# 18__-2.net
KiCad netlist of a schematic drawn in Altium Designer
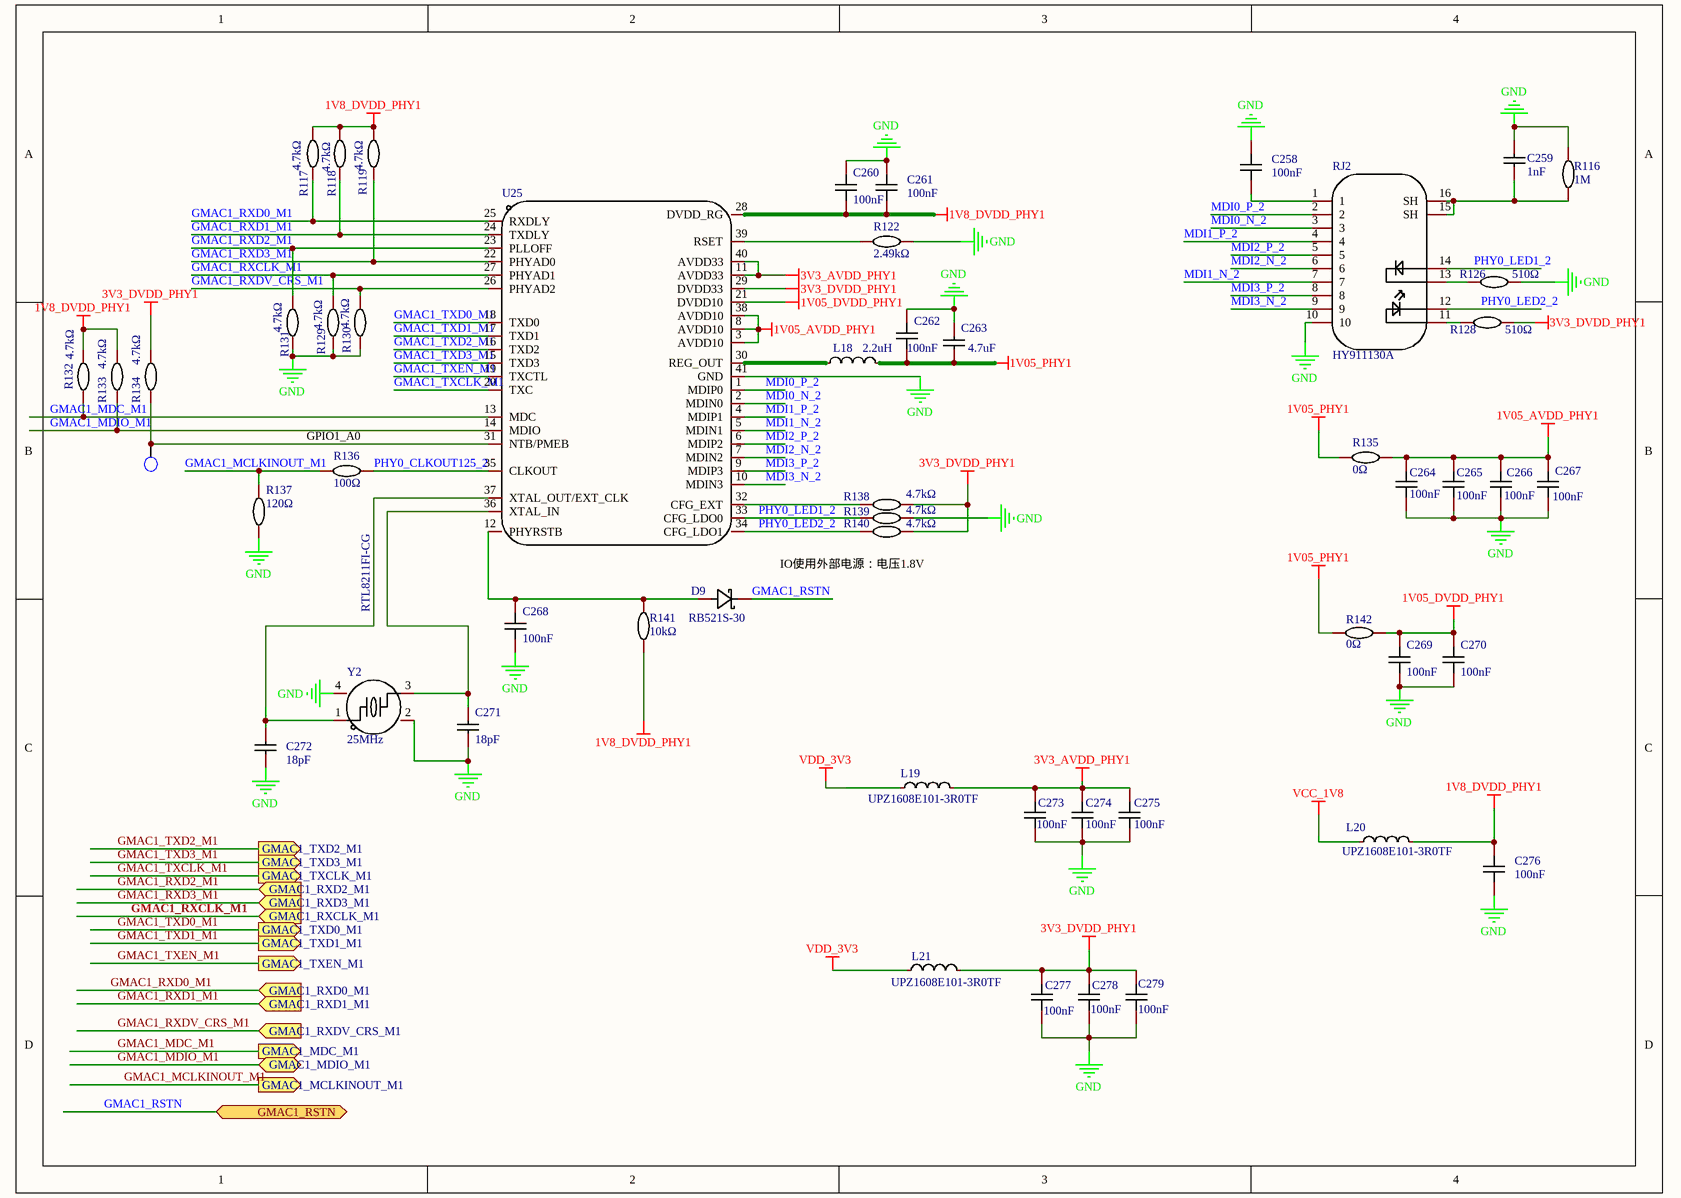
[diagram p0: 18_网口接口-2.schdoc]

(export (version "E")
  (design (tool "Eeschema 10.0.6"))
  (components
    (comp (ref "C258")
      (value "100nF")
      (footprint "C0603")
      (fields
        (field (name "NAME") "100nF")
        (field (name "MANUFACTURER") "YAGEO(国巨)")
        (field (name "MANUFACTURER PART") "CC0603KRX7R9BB104")
        (field (name "TOLERANCE") "±10%")
      )
      (libsource (lib "altium-import") (part "root_1_CC0603KRX7R9BB104_"))
    )
    (comp (ref "C259")
      (value "1nF")
      (footprint "C0603")
      (fields
        (field (name "NAME") "1nF")
        (field (name "MANUFACTURER") "YAGEO(国巨)")
        (field (name "MANUFACTURER PART") "CC0603KRX7R9BB102")
        (field (name "TOLERANCE") "±10%")
      )
      (libsource (lib "altium-import") (part "root_3_CC0603KRX7R9BB102_"))
    )
    (comp (ref "C260")
      (value "100nF")
      (footprint "C0603")
      (fields
        (field (name "NAME") "100nF")
        (field (name "MANUFACTURER") "YAGEO(国巨)")
        (field (name "MANUFACTURER PART") "CC0603KRX7R9BB104")
        (field (name "TOLERANCE") "±10%")
      )
      (libsource (lib "altium-import") (part "root_1_CC0603KRX7R9BB104_"))
    )
    (comp (ref "C261")
      (value "100nF")
      (footprint "C0603")
      (fields
        (field (name "NAME") "100nF")
        (field (name "MANUFACTURER") "YAGEO(国巨)")
        (field (name "MANUFACTURER PART") "CC0603KRX7R9BB104")
        (field (name "TOLERANCE") "±10%")
      )
      (libsource (lib "altium-import") (part "root_1_CC0603KRX7R9BB104_"))
    )
    (comp (ref "C262")
      (value "100nF")
      (footprint "C0603")
      (fields
        (field (name "NAME") "100nF")
        (field (name "MANUFACTURER") "YAGEO(国巨)")
        (field (name "MANUFACTURER PART") "CC0603KRX7R9BB104")
        (field (name "TOLERANCE") "±10%")
      )
      (libsource (lib "altium-import") (part "root_1_CC0603KRX7R9BB104_"))
    )
    (comp (ref "C263")
      (value "4.7uF")
      (footprint "C0603")
      (fields
        (field (name "NAME") "4.7uF")
        (field (name "MANUFACTURER PART") "CL10A475KO8NNNC")
        (field (name "MANUFACTURER") "SAMSUNG(三星)")
        (field (name "TOLERANCE") "±10%")
      )
      (libsource (lib "altium-import") (part "root_1_CL10A475KO8NNNC_"))
    )
    (comp (ref "C264")
      (value "100nF")
      (footprint "C0603")
      (fields
        (field (name "NAME") "100nF")
        (field (name "MANUFACTURER") "YAGEO(国巨)")
        (field (name "MANUFACTURER PART") "CC0603KRX7R9BB104")
        (field (name "TOLERANCE") "±10%")
      )
      (libsource (lib "altium-import") (part "root_1_CC0603KRX7R9BB104_"))
    )
    (comp (ref "C265")
      (value "100nF")
      (footprint "C0603")
      (fields
        (field (name "NAME") "100nF")
        (field (name "MANUFACTURER") "YAGEO(国巨)")
        (field (name "MANUFACTURER PART") "CC0603KRX7R9BB104")
        (field (name "TOLERANCE") "±10%")
      )
      (libsource (lib "altium-import") (part "root_1_CC0603KRX7R9BB104_"))
    )
    (comp (ref "C266")
      (value "100nF")
      (footprint "C0603")
      (fields
        (field (name "NAME") "100nF")
        (field (name "MANUFACTURER") "YAGEO(国巨)")
        (field (name "MANUFACTURER PART") "CC0603KRX7R9BB104")
        (field (name "TOLERANCE") "±10%")
      )
      (libsource (lib "altium-import") (part "root_1_CC0603KRX7R9BB104_"))
    )
    (comp (ref "C267")
      (value "100nF")
      (footprint "C0603")
      (fields
        (field (name "NAME") "100nF")
        (field (name "MANUFACTURER") "YAGEO(国巨)")
        (field (name "MANUFACTURER PART") "CC0603KRX7R9BB104")
        (field (name "TOLERANCE") "±10%")
      )
      (libsource (lib "altium-import") (part "root_1_CC0603KRX7R9BB104_"))
    )
    (comp (ref "C268")
      (value "100nF")
      (footprint "C0603")
      (fields
        (field (name "NAME") "100nF")
        (field (name "MANUFACTURER") "YAGEO(国巨)")
        (field (name "MANUFACTURER PART") "CC0603KRX7R9BB104")
        (field (name "TOLERANCE") "±10%")
      )
      (libsource (lib "altium-import") (part "root_1_CC0603KRX7R9BB104_"))
    )
    (comp (ref "C269")
      (value "100nF")
      (footprint "C0603")
      (fields
        (field (name "NAME") "100nF")
        (field (name "MANUFACTURER") "YAGEO(国巨)")
        (field (name "MANUFACTURER PART") "CC0603KRX7R9BB104")
        (field (name "TOLERANCE") "±10%")
      )
      (libsource (lib "altium-import") (part "root_1_CC0603KRX7R9BB104_"))
    )
    (comp (ref "C270")
      (value "100nF")
      (footprint "C0603")
      (fields
        (field (name "NAME") "100nF")
        (field (name "MANUFACTURER") "YAGEO(国巨)")
        (field (name "MANUFACTURER PART") "CC0603KRX7R9BB104")
        (field (name "TOLERANCE") "±10%")
      )
      (libsource (lib "altium-import") (part "root_1_CC0603KRX7R9BB104_"))
    )
    (comp (ref "C271")
      (value "18pF")
      (footprint "C0603")
      (fields
        (field (name "NAME") "18pF")
        (field (name "MANUFACTURER") "SAMSUNG(三星)")
        (field (name "MANUFACTURER PART") "CL10C180JB8NNNC")
        (field (name "TOLERANCE") "±5%")
      )
      (libsource (lib "altium-import") (part "root_3_CL10C180JB8NNNC_"))
    )
    (comp (ref "C272")
      (value "18pF")
      (footprint "C0603")
      (fields
        (field (name "NAME") "18pF")
        (field (name "MANUFACTURER") "SAMSUNG(三星)")
        (field (name "MANUFACTURER PART") "CL10C180JB8NNNC")
        (field (name "TOLERANCE") "±5%")
      )
      (libsource (lib "altium-import") (part "root_3_CL10C180JB8NNNC_"))
    )
    (comp (ref "C273")
      (value "100nF")
      (footprint "C0603")
      (fields
        (field (name "NAME") "100nF")
        (field (name "MANUFACTURER") "YAGEO(国巨)")
        (field (name "MANUFACTURER PART") "CC0603KRX7R9BB104")
        (field (name "TOLERANCE") "±10%")
      )
      (libsource (lib "altium-import") (part "root_1_CC0603KRX7R9BB104_"))
    )
    (comp (ref "C274")
      (value "100nF")
      (footprint "C0603")
      (fields
        (field (name "NAME") "100nF")
        (field (name "MANUFACTURER") "YAGEO(国巨)")
        (field (name "MANUFACTURER PART") "CC0603KRX7R9BB104")
        (field (name "TOLERANCE") "±10%")
      )
      (libsource (lib "altium-import") (part "root_1_CC0603KRX7R9BB104_"))
    )
    (comp (ref "C275")
      (value "100nF")
      (footprint "C0603")
      (fields
        (field (name "NAME") "100nF")
        (field (name "MANUFACTURER") "YAGEO(国巨)")
        (field (name "MANUFACTURER PART") "CC0603KRX7R9BB104")
        (field (name "TOLERANCE") "±10%")
      )
      (libsource (lib "altium-import") (part "root_1_CC0603KRX7R9BB104_"))
    )
    (comp (ref "C276")
      (value "100nF")
      (footprint "C0603")
      (fields
        (field (name "NAME") "100nF")
        (field (name "MANUFACTURER") "YAGEO(国巨)")
        (field (name "MANUFACTURER PART") "CC0603KRX7R9BB104")
        (field (name "TOLERANCE") "±10%")
      )
      (libsource (lib "altium-import") (part "root_1_CC0603KRX7R9BB104_"))
    )
    (comp (ref "C277")
      (value "100nF")
      (footprint "C0603")
      (fields
        (field (name "NAME") "100nF")
        (field (name "MANUFACTURER") "YAGEO(国巨)")
        (field (name "MANUFACTURER PART") "CC0603KRX7R9BB104")
        (field (name "TOLERANCE") "±10%")
      )
      (libsource (lib "altium-import") (part "root_1_CC0603KRX7R9BB104_"))
    )
    (comp (ref "C278")
      (value "100nF")
      (footprint "C0603")
      (fields
        (field (name "NAME") "100nF")
        (field (name "MANUFACTURER") "YAGEO(国巨)")
        (field (name "MANUFACTURER PART") "CC0603KRX7R9BB104")
        (field (name "TOLERANCE") "±10%")
      )
      (libsource (lib "altium-import") (part "root_1_CC0603KRX7R9BB104_"))
    )
    (comp (ref "C279")
      (value "100nF")
      (footprint "C0603")
      (fields
        (field (name "NAME") "100nF")
        (field (name "MANUFACTURER") "YAGEO(国巨)")
        (field (name "MANUFACTURER PART") "CC0603KRX7R9BB104")
        (field (name "TOLERANCE") "±10%")
      )
      (libsource (lib "altium-import") (part "root_1_CC0603KRX7R9BB104_"))
    )
    (comp (ref "D9")
      (value "RB521S-30")
      (footprint "SOD-523_L1.2-W0.8-LS1.6-RD")
      (fields (field (name "NAME") "RB521S-30") (field (name "MANUFACTURER") "TWGMC(台湾迪嘉)"))
      (libsource (lib "altium-import") (part "root_2_RB521S-30_C727120_"))
    )
    (comp (ref "L18")
      (value "2.2uH")
      (footprint "IND-SMD_L2.5-W2.0-VLS252012CX-150M")
      (fields
        (field (name "NAME") "2.2uH")
        (field (name "MANUFACTURER") "cjiang(长江微电)")
        (field (name "MANUFACTURER PART") "FXLB252012-2R2-M")
        (field (name "TOLERANCE") "±20%")
      )
      (libsource (lib "altium-import") (part "root_0_FXLB252012-2R2-M_"))
    )
    (comp (ref "L19")
      (value "UPZ1608E101-3R0TF")
      (footprint "L0603")
      (fields
        (field (name "NAME") "UPZ1608E101-3R0TF")
        (field (name "MANUFACTURER") "Sunlord(顺络)")
        (field (name "TOLERANCE") "±25%")
      )
      (libsource (lib "altium-import") (part "root_0_mirrored_UPZ1608E101-3R0TF_"))
    )
    (comp (ref "L20")
      (value "UPZ1608E101-3R0TF")
      (footprint "L0603")
      (fields
        (field (name "NAME") "UPZ1608E101-3R0TF")
        (field (name "MANUFACTURER") "Sunlord(顺络)")
        (field (name "TOLERANCE") "±25%")
      )
      (libsource (lib "altium-import") (part "root_0_mirrored_UPZ1608E101-3R0TF_"))
    )
    (comp (ref "L21")
      (value "UPZ1608E101-3R0TF")
      (footprint "L0603")
      (fields
        (field (name "NAME") "UPZ1608E101-3R0TF")
        (field (name "MANUFACTURER") "Sunlord(顺络)")
        (field (name "TOLERANCE") "±25%")
      )
      (libsource (lib "altium-import") (part "root_0_mirrored_UPZ1608E101-3R0TF_"))
    )
    (comp (ref "R116")
      (value "1M")
      (footprint "R0805")
      (fields (field (name "NAME") "1M"))
      (libsource (lib "altium-import") (part "root_3_Res_0805_"))
    )
    (comp (ref "R117")
      (value "4.7kΩ")
      (footprint "R0603")
      (fields
        (field (name "NAME") "4.7kΩ")
        (field (name "MANUFACTURER") "UNI-ROYAL(厚声)")
        (field (name "MANUFACTURER PART") "0603WAF4701T5E")
        (field (name "TOLERANCE") "±1%")
      )
      (libsource (lib "altium-import") (part "root_1_0603WAF4701T5E_"))
    )
    (comp (ref "R118")
      (value "4.7kΩ")
      (footprint "R0603")
      (fields
        (field (name "NAME") "4.7kΩ")
        (field (name "MANUFACTURER") "UNI-ROYAL(厚声)")
        (field (name "MANUFACTURER PART") "0603WAF4701T5E")
        (field (name "TOLERANCE") "±1%")
      )
      (libsource (lib "altium-import") (part "root_1_0603WAF4701T5E_"))
    )
    (comp (ref "R119")
      (value "4.7kΩ")
      (footprint "R0603")
      (fields
        (field (name "NAME") "4.7kΩ")
        (field (name "MANUFACTURER") "UNI-ROYAL(厚声)")
        (field (name "MANUFACTURER PART") "0603WAF4701T5E")
        (field (name "TOLERANCE") "±1%")
      )
      (libsource (lib "altium-import") (part "root_1_0603WAF4701T5E_"))
    )
    (comp (ref "R122")
      (value "2.49kΩ")
      (footprint "R0603")
      (fields
        (field (name "NAME") "2.49kΩ")
        (field (name "MANUFACTURER") "UNI-ROYAL(厚声)")
        (field (name "MANUFACTURER PART") "0603WAF2491T5E")
        (field (name "TOLERANCE") "±1%")
      )
      (libsource (lib "altium-import") (part "root_0_0603WAF2491T5E_"))
    )
    (comp (ref "R126")
      (value "510Ω")
      (footprint "R0603")
      (fields
        (field (name "NAME") "510Ω")
        (field (name "MANUFACTURER") "UNI-ROYAL(厚声)")
        (field (name "MANUFACTURER PART") "0603WAF5100T5E")
        (field (name "TOLERANCE") "±1%")
      )
      (libsource (lib "altium-import") (part "root_0_0603WAF5100T5E_"))
    )
    (comp (ref "R128")
      (value "510Ω")
      (footprint "R0603")
      (fields
        (field (name "NAME") "510Ω")
        (field (name "MANUFACTURER") "UNI-ROYAL(厚声)")
        (field (name "MANUFACTURER PART") "0603WAF5100T5E")
        (field (name "TOLERANCE") "±1%")
      )
      (libsource (lib "altium-import") (part "root_0_0603WAF5100T5E_"))
    )
    (comp (ref "R129")
      (value "4.7kΩ")
      (footprint "R0603")
      (fields
        (field (name "NAME") "4.7kΩ")
        (field (name "MANUFACTURER") "UNI-ROYAL(厚声)")
        (field (name "MANUFACTURER PART") "0603WAF4701T5E")
        (field (name "TOLERANCE") "±1%")
      )
      (libsource (lib "altium-import") (part "root_1_0603WAF4701T5E_"))
    )
    (comp (ref "R130")
      (value "4.7kΩ")
      (footprint "R0603")
      (fields
        (field (name "NAME") "4.7kΩ")
        (field (name "MANUFACTURER") "UNI-ROYAL(厚声)")
        (field (name "MANUFACTURER PART") "0603WAF4701T5E")
        (field (name "TOLERANCE") "±1%")
      )
      (libsource (lib "altium-import") (part "root_1_0603WAF4701T5E_"))
    )
    (comp (ref "R131")
      (value "4.7kΩ")
      (footprint "R0603")
      (fields
        (field (name "NAME") "4.7kΩ")
        (field (name "MANUFACTURER") "UNI-ROYAL(厚声)")
        (field (name "MANUFACTURER PART") "0603WAF4701T5E")
        (field (name "TOLERANCE") "±1%")
      )
      (libsource (lib "altium-import") (part "root_1_0603WAF4701T5E_"))
    )
    (comp (ref "R132")
      (value "4.7kΩ")
      (footprint "R0603")
      (fields
        (field (name "NAME") "4.7kΩ")
        (field (name "MANUFACTURER") "UNI-ROYAL(厚声)")
        (field (name "MANUFACTURER PART") "0603WAF4701T5E")
        (field (name "TOLERANCE") "±1%")
      )
      (libsource (lib "altium-import") (part "root_1_0603WAF4701T5E_"))
    )
    (comp (ref "R133")
      (value "4.7kΩ")
      (footprint "R0603")
      (fields
        (field (name "NAME") "4.7kΩ")
        (field (name "MANUFACTURER") "UNI-ROYAL(厚声)")
        (field (name "MANUFACTURER PART") "0603WAF4701T5E")
        (field (name "TOLERANCE") "±1%")
      )
      (libsource (lib "altium-import") (part "root_1_0603WAF4701T5E_"))
    )
    (comp (ref "R134")
      (value "4.7kΩ")
      (footprint "R0603")
      (fields
        (field (name "NAME") "4.7kΩ")
        (field (name "MANUFACTURER") "UNI-ROYAL(厚声)")
        (field (name "MANUFACTURER PART") "0603WAF4701T5E")
        (field (name "TOLERANCE") "±1%")
      )
      (libsource (lib "altium-import") (part "root_1_0603WAF4701T5E_"))
    )
    (comp (ref "R135")
      (value "0Ω")
      (footprint "R0603")
      (fields
        (field (name "NAME") "0Ω")
        (field (name "MANUFACTURER") "UNI-ROYAL(厚声)")
        (field (name "MANUFACTURER PART") "0603WAF0000T5E")
        (field (name "TOLERANCE") "±1%")
      )
      (libsource (lib "altium-import") (part "root_0_0603WAF0000T5E_"))
    )
    (comp (ref "R136")
      (value "100Ω")
      (footprint "R0603")
      (fields
        (field (name "NAME") "100Ω")
        (field (name "MANUFACTURER") "UNI-ROYAL(厚声)")
        (field (name "MANUFACTURER PART") "0603WAF1000T5E")
        (field (name "TOLERANCE") "±1%")
      )
      (libsource (lib "altium-import") (part "root_0_0603WAF1000T5E_"))
    )
    (comp (ref "R137")
      (value "120Ω")
      (footprint "R0603")
      (fields
        (field (name "NAME") "120Ω")
        (field (name "MANUFACTURER") "UNI-ROYAL(厚声)")
        (field (name "MANUFACTURER PART") "0603WAF1200T5E")
        (field (name "TOLERANCE") "±1%")
      )
      (libsource (lib "altium-import") (part "root_1_0603WAF1200T5E_"))
    )
    (comp (ref "R138")
      (value "4.7kΩ")
      (footprint "R0603")
      (fields
        (field (name "NAME") "4.7kΩ")
        (field (name "MANUFACTURER") "UNI-ROYAL(厚声)")
        (field (name "MANUFACTURER PART") "0603WAF4701T5E")
        (field (name "TOLERANCE") "±1%")
      )
      (libsource (lib "altium-import") (part "root_0_0603WAF4701T5E_"))
    )
    (comp (ref "R139")
      (value "4.7kΩ")
      (footprint "R0603")
      (fields
        (field (name "NAME") "4.7kΩ")
        (field (name "MANUFACTURER") "UNI-ROYAL(厚声)")
        (field (name "MANUFACTURER PART") "0603WAF4701T5E")
        (field (name "TOLERANCE") "±1%")
      )
      (libsource (lib "altium-import") (part "root_0_0603WAF4701T5E_"))
    )
    (comp (ref "R140")
      (value "4.7kΩ")
      (footprint "R0603")
      (fields
        (field (name "NAME") "4.7kΩ")
        (field (name "MANUFACTURER") "UNI-ROYAL(厚声)")
        (field (name "MANUFACTURER PART") "0603WAF4701T5E")
        (field (name "TOLERANCE") "±1%")
      )
      (libsource (lib "altium-import") (part "root_0_0603WAF4701T5E_"))
    )
    (comp (ref "R141")
      (value "10kΩ")
      (footprint "R0603")
      (fields
        (field (name "NAME") "10kΩ")
        (field (name "MANUFACTURER") "UNI-ROYAL(厚声)")
        (field (name "MANUFACTURER PART") "0603WAF1002T5E")
        (field (name "TOLERANCE") "±1%")
      )
      (libsource (lib "altium-import") (part "root_3_0603WAF1002T5E_"))
    )
    (comp (ref "R142")
      (value "0Ω")
      (footprint "R0603")
      (fields
        (field (name "NAME") "0Ω")
        (field (name "MANUFACTURER") "UNI-ROYAL(厚声)")
        (field (name "MANUFACTURER PART") "0603WAF0000T5E")
        (field (name "TOLERANCE") "±1%")
      )
      (libsource (lib "altium-import") (part "root_2_0603WAF0000T5E_"))
    )
    (comp (ref "RJ2")
      (value "HY911130A")
      (footprint "RJ45-TH_10P-P2.54-S2.54_L16.1-W21.4_HY911130A")
      (fields (field (name "NAME") "HY911130A") (field (name "MANUFACTURER") "HANRUN(汉仁)"))
      (libsource (lib "altium-import") (part "root_0_HY911130A_"))
    )
    (comp (ref "TP2") (value "TP") (footprint "TP_0R70") (libsource (lib "RK3568核心板") (part "TP")))
    (comp (ref "U25")
      (value "RTL8211FI-CG")
      (footprint "QFN-40_L5.0-W5.0-P0.40-BL-EP3.7")
      (fields (field (name "NAME") "RTL8211FI-CG") (field (name "MANUFACTURER") "REALTEK(瑞昱)"))
      (libsource (lib "altium-import") (part "root_0_RTL8211FI-CG_"))
    )
    (comp (ref "Y2")
      (value "25MHz")
      (footprint "CRYSTAL-SMD_4P-L3.2-W2.5-BL")
      (fields
        (field (name "NAME") "25MHz")
        (field (name "MANUFACTURER") "YXC(扬兴晶振)")
        (field (name "MANUFACTURER PART") "XL2EL89CSI-111YLC-25M")
      )
      (libsource (lib "altium-import") (part "root_0_XL2EL89CSI-111YLC-25M_"))
    )
  )
  (nets
    (net (code "1") (name "/GMAC1_MCLKINOUT_M1") (class "Default")
      (node (ref "R136") (pin "1") (pinfunction "1_1") (pintype "passive"))
      (node (ref "R137") (pin "2") (pinfunction "2_2") (pintype "passive"))
    )
    (net (code "2") (name "/GMAC1_MDC_M1") (class "Default")
      (node (ref "R132") (pin "1") (pinfunction "1_1") (pintype "passive"))
      (node (ref "U25") (pin "13") (pinfunction "MDC_13") (pintype "passive"))
    )
    (net (code "3") (name "/GMAC1_MDIO_M1") (class "Default")
      (node (ref "R133") (pin "1") (pinfunction "1_1") (pintype "passive"))
      (node (ref "U25") (pin "14") (pinfunction "MDIO_14") (pintype "passive"))
    )
    (net (code "4") (name "/GMAC1_RSTN") (class "Default")
      (node (ref "D9") (pin "1") (pinfunction "K_1") (pintype "passive"))
    )
    (net (code "5") (name "/GMAC1_RXCLK_M1") (class "Default")
      (node (ref "R129") (pin "2") (pinfunction "2_2") (pintype "passive"))
      (node (ref "U25") (pin "27") (pinfunction "PHYAD1_27") (pintype "passive"))
    )
    (net (code "6") (name "/GMAC1_RXD0_M1") (class "Default")
      (node (ref "R117") (pin "1") (pinfunction "1_1") (pintype "passive"))
      (node (ref "U25") (pin "25") (pinfunction "RXDLY_25") (pintype "passive"))
    )
    (net (code "7") (name "/GMAC1_RXD1_M1") (class "Default")
      (node (ref "R118") (pin "1") (pinfunction "1_1") (pintype "passive"))
      (node (ref "U25") (pin "24") (pinfunction "TXDLY_24") (pintype "passive"))
    )
    (net (code "8") (name "/GMAC1_RXD2_M1") (class "Default")
      (node (ref "R131") (pin "2") (pinfunction "2_2") (pintype "passive"))
      (node (ref "U25") (pin "23") (pinfunction "PLLOFF_23") (pintype "passive"))
    )
    (net (code "9") (name "/GMAC1_RXD3_M1") (class "Default")
      (node (ref "R119") (pin "1") (pinfunction "1_1") (pintype "passive"))
      (node (ref "U25") (pin "22") (pinfunction "PHYAD0_22") (pintype "passive"))
    )
    (net (code "10") (name "/GMAC1_RXDV_CRS_M1") (class "Default")
      (node (ref "R130") (pin "2") (pinfunction "2_2") (pintype "passive"))
      (node (ref "U25") (pin "26") (pinfunction "PHYAD2_26") (pintype "passive"))
    )
    (net (code "11") (name "/GMAC1_TXCLK_M1") (class "Default")
      (node (ref "U25") (pin "20") (pinfunction "TXC_20") (pintype "passive"))
    )
    (net (code "12") (name "/GMAC1_TXD0_M1") (class "Default")
      (node (ref "U25") (pin "18") (pinfunction "TXD0_18") (pintype "passive"))
    )
    (net (code "13") (name "/GMAC1_TXD1_M1") (class "Default")
      (node (ref "U25") (pin "17") (pinfunction "TXD1_17") (pintype "passive"))
    )
    (net (code "14") (name "/GMAC1_TXD2_M1") (class "Default")
      (node (ref "U25") (pin "16") (pinfunction "TXD2_16") (pintype "passive"))
    )
    (net (code "15") (name "/GMAC1_TXD3_M1") (class "Default")
      (node (ref "U25") (pin "15") (pinfunction "TXD3_15") (pintype "passive"))
    )
    (net (code "16") (name "/GMAC1_TXEN_M1") (class "Default")
      (node (ref "U25") (pin "19") (pinfunction "TXCTL_19") (pintype "passive"))
    )
    (net (code "17") (name "/MDI0_N_2") (class "Default")
      (node (ref "RJ2") (pin "3") (pinfunction "3_3") (pintype "passive"))
      (node (ref "U25") (pin "2") (pinfunction "MDIN0_2") (pintype "passive"))
    )
    (net (code "18") (name "/MDI0_P_2") (class "Default")
      (node (ref "RJ2") (pin "2") (pinfunction "2_2") (pintype "passive"))
      (node (ref "U25") (pin "1") (pinfunction "MDIP0_1") (pintype "passive"))
    )
    (net (code "19") (name "/MDI1_N_2") (class "Default")
      (node (ref "RJ2") (pin "7") (pinfunction "7_7") (pintype "passive"))
      (node (ref "U25") (pin "5") (pinfunction "MDIN1_5") (pintype "passive"))
    )
    (net (code "20") (name "/MDI1_P_2") (class "Default")
      (node (ref "RJ2") (pin "4") (pinfunction "4_4") (pintype "passive"))
      (node (ref "U25") (pin "4") (pinfunction "MDIP1_4") (pintype "passive"))
    )
    (net (code "21") (name "/MDI2_N_2") (class "Default")
      (node (ref "RJ2") (pin "6") (pinfunction "6_6") (pintype "passive"))
      (node (ref "U25") (pin "7") (pinfunction "MDIN2_7") (pintype "passive"))
    )
    (net (code "22") (name "/MDI2_P_2") (class "Default")
      (node (ref "RJ2") (pin "5") (pinfunction "5_5") (pintype "passive"))
      (node (ref "U25") (pin "6") (pinfunction "MDIP2_6") (pintype "passive"))
    )
    (net (code "23") (name "/MDI3_N_2") (class "Default")
      (node (ref "RJ2") (pin "9") (pinfunction "9_9") (pintype "passive"))
      (node (ref "U25") (pin "10") (pinfunction "MDIN3_10") (pintype "passive"))
    )
    (net (code "24") (name "/MDI3_P_2") (class "Default")
      (node (ref "RJ2") (pin "8") (pinfunction "8_8") (pintype "passive"))
      (node (ref "U25") (pin "9") (pinfunction "MDIP3_9") (pintype "passive"))
    )
    (net (code "25") (name "/PHY0_CLKOUT125_2") (class "Default")
      (node (ref "R136") (pin "2") (pinfunction "2_2") (pintype "passive"))
      (node (ref "U25") (pin "35") (pinfunction "CLKOUT_35") (pintype "passive"))
    )
    (net (code "26") (name "/PHY0_LED1_2") (class "Default")
      (node (ref "R139") (pin "1") (pinfunction "1_1") (pintype "passive"))
      (node (ref "RJ2") (pin "14") (pinfunction "14_14") (pintype "passive"))
      (node (ref "U25") (pin "33") (pinfunction "CFG_LDO0_33") (pintype "passive"))
    )
    (net (code "27") (name "/PHY0_LED2_2") (class "Default")
      (node (ref "R140") (pin "1") (pinfunction "1_1") (pintype "passive"))
      (node (ref "RJ2") (pin "12") (pinfunction "12_12") (pintype "passive"))
      (node (ref "U25") (pin "34") (pinfunction "CFG_LDO1_34") (pintype "passive"))
    )
    (net (code "28") (name "1V05_AVDD_PHY1") (class "Default")
      (node (ref "C264") (pin "2") (pinfunction "2_2") (pintype "passive"))
      (node (ref "C265") (pin "2") (pinfunction "2_2") (pintype "passive"))
      (node (ref "C266") (pin "2") (pinfunction "2_2") (pintype "passive"))
      (node (ref "C267") (pin "2") (pinfunction "2_2") (pintype "passive"))
      (node (ref "R135") (pin "2") (pinfunction "2_2") (pintype "passive"))
      (node (ref "U25") (pin "3") (pinfunction "AVDD10_3") (pintype "passive"))
      (node (ref "U25") (pin "38") (pinfunction "AVDD10_38") (pintype "passive"))
      (node (ref "U25") (pin "8") (pinfunction "AVDD10_8") (pintype "passive"))
    )
    (net (code "29") (name "1V05_DVDD_PHY1") (class "Default")
      (node (ref "C269") (pin "2") (pinfunction "2_2") (pintype "passive"))
      (node (ref "C270") (pin "2") (pinfunction "2_2") (pintype "passive"))
      (node (ref "R142") (pin "1") (pinfunction "1_1") (pintype "passive"))
      (node (ref "U25") (pin "21") (pinfunction "DVDD10_21") (pintype "passive"))
    )
    (net (code "30") (name "1V05_PHY1") (class "Default")
      (node (ref "C262") (pin "1") (pinfunction "1_1") (pintype "passive"))
      (node (ref "C263") (pin "1") (pinfunction "1_1") (pintype "passive"))
      (node (ref "L18") (pin "2") (pinfunction "2_2") (pintype "passive"))
      (node (ref "R135") (pin "1") (pinfunction "1_1") (pintype "passive"))
      (node (ref "R142") (pin "2") (pinfunction "2_2") (pintype "passive"))
    )
    (net (code "31") (name "1V8_DVDD_PHY1") (class "Default")
      (node (ref "C260") (pin "1") (pinfunction "1_1") (pintype "passive"))
      (node (ref "C261") (pin "1") (pinfunction "1_1") (pintype "passive"))
      (node (ref "C276") (pin "2") (pinfunction "2_2") (pintype "passive"))
      (node (ref "L20") (pin "1") (pinfunction "1_1") (pintype "passive"))
      (node (ref "R117") (pin "2") (pinfunction "2_2") (pintype "passive"))
      (node (ref "R118") (pin "2") (pinfunction "2_2") (pintype "passive"))
      (node (ref "R119") (pin "2") (pinfunction "2_2") (pintype "passive"))
      (node (ref "R132") (pin "2") (pinfunction "2_2") (pintype "passive"))
      (node (ref "R133") (pin "2") (pinfunction "2_2") (pintype "passive"))
      (node (ref "R141") (pin "2") (pinfunction "2_2") (pintype "passive"))
      (node (ref "U25") (pin "28") (pinfunction "DVDD_RG_28") (pintype "passive"))
    )
    (net (code "32") (name "3V3_AVDD_PHY1") (class "Default")
      (node (ref "C273") (pin "2") (pinfunction "2_2") (pintype "passive"))
      (node (ref "C274") (pin "2") (pinfunction "2_2") (pintype "passive"))
      (node (ref "C275") (pin "2") (pinfunction "2_2") (pintype "passive"))
      (node (ref "L19") (pin "1") (pinfunction "1_1") (pintype "passive"))
      (node (ref "U25") (pin "11") (pinfunction "AVDD33_11") (pintype "passive"))
      (node (ref "U25") (pin "40") (pinfunction "AVDD33_40") (pintype "passive"))
    )
    (net (code "33") (name "3V3_DVDD_PHY1") (class "Default")
      (node (ref "C277") (pin "2") (pinfunction "2_2") (pintype "passive"))
      (node (ref "C278") (pin "2") (pinfunction "2_2") (pintype "passive"))
      (node (ref "C279") (pin "2") (pinfunction "2_2") (pintype "passive"))
      (node (ref "L21") (pin "1") (pinfunction "1_1") (pintype "passive"))
      (node (ref "R128") (pin "2") (pinfunction "2_2") (pintype "passive"))
      (node (ref "R134") (pin "2") (pinfunction "2_2") (pintype "passive"))
      (node (ref "R138") (pin "2") (pinfunction "2_2") (pintype "passive"))
      (node (ref "R140") (pin "2") (pinfunction "2_2") (pintype "passive"))
      (node (ref "U25") (pin "29") (pinfunction "DVDD33_29") (pintype "passive"))
    )
    (net (code "34") (name "GND") (class "Default")
      (node (ref "C258") (pin "2") (pinfunction "2_2") (pintype "passive"))
      (node (ref "C259") (pin "1") (pinfunction "1_1") (pintype "passive"))
      (node (ref "C260") (pin "2") (pinfunction "2_2") (pintype "passive"))
      (node (ref "C261") (pin "2") (pinfunction "2_2") (pintype "passive"))
      (node (ref "C262") (pin "2") (pinfunction "2_2") (pintype "passive"))
      (node (ref "C263") (pin "2") (pinfunction "2_2") (pintype "passive"))
      (node (ref "C264") (pin "1") (pinfunction "1_1") (pintype "passive"))
      (node (ref "C265") (pin "1") (pinfunction "1_1") (pintype "passive"))
      (node (ref "C266") (pin "1") (pinfunction "1_1") (pintype "passive"))
      (node (ref "C267") (pin "1") (pinfunction "1_1") (pintype "passive"))
      (node (ref "C268") (pin "1") (pinfunction "1_1") (pintype "passive"))
      (node (ref "C269") (pin "1") (pinfunction "1_1") (pintype "passive"))
      (node (ref "C270") (pin "1") (pinfunction "1_1") (pintype "passive"))
      (node (ref "C271") (pin "2") (pinfunction "2_2") (pintype "passive"))
      (node (ref "C272") (pin "2") (pinfunction "2_2") (pintype "passive"))
      (node (ref "C273") (pin "1") (pinfunction "1_1") (pintype "passive"))
      (node (ref "C274") (pin "1") (pinfunction "1_1") (pintype "passive"))
      (node (ref "C275") (pin "1") (pinfunction "1_1") (pintype "passive"))
      (node (ref "C276") (pin "1") (pinfunction "1_1") (pintype "passive"))
      (node (ref "C277") (pin "1") (pinfunction "1_1") (pintype "passive"))
      (node (ref "C278") (pin "1") (pinfunction "1_1") (pintype "passive"))
      (node (ref "C279") (pin "1") (pinfunction "1_1") (pintype "passive"))
      (node (ref "R116") (pin "1") (pinfunction "1_1") (pintype "passive"))
      (node (ref "R122") (pin "2") (pinfunction "2_2") (pintype "passive"))
      (node (ref "R126") (pin "2") (pinfunction "2_2") (pintype "passive"))
      (node (ref "R129") (pin "1") (pinfunction "1_1") (pintype "passive"))
      (node (ref "R130") (pin "1") (pinfunction "1_1") (pintype "passive"))
      (node (ref "R131") (pin "1") (pinfunction "1_1") (pintype "passive"))
      (node (ref "R137") (pin "1") (pinfunction "1_1") (pintype "passive"))
      (node (ref "R139") (pin "2") (pinfunction "2_2") (pintype "passive"))
      (node (ref "RJ2") (pin "10") (pinfunction "10_10") (pintype "passive"))
      (node (ref "U25") (pin "41") (pinfunction "GND_41") (pintype "passive"))
      (node (ref "Y2") (pin "2") (pinfunction "GND_2") (pintype "passive"))
      (node (ref "Y2") (pin "4") (pinfunction "GND_4") (pintype "passive"))
    )
    (net (code "35") (name "Net-(C258-Pad1)") (class "Default")
      (node (ref "C258") (pin "1") (pinfunction "1_1") (pintype "passive"))
      (node (ref "RJ2") (pin "1") (pinfunction "1_1") (pintype "passive"))
    )
    (net (code "36") (name "Net-(C259-Pad2)") (class "Default")
      (node (ref "C259") (pin "2") (pinfunction "2_2") (pintype "passive"))
      (node (ref "R116") (pin "2") (pinfunction "2_2") (pintype "passive"))
      (node (ref "RJ2") (pin "15") (pinfunction "SH_15") (pintype "passive"))
      (node (ref "RJ2") (pin "16") (pinfunction "SH_16") (pintype "passive"))
    )
    (net (code "37") (name "Net-(D9-A)") (class "Default")
      (node (ref "C268") (pin "2") (pinfunction "2_2") (pintype "passive"))
      (node (ref "D9") (pin "2") (pinfunction "A_2") (pintype "passive"))
      (node (ref "R141") (pin "1") (pinfunction "1_1") (pintype "passive"))
      (node (ref "U25") (pin "12") (pinfunction "PHYRSTB_12") (pintype "passive"))
    )
    (net (code "38") (name "Net-(R126-Pad1)") (class "Default")
      (node (ref "R126") (pin "1") (pinfunction "1_1") (pintype "passive"))
      (node (ref "RJ2") (pin "13") (pinfunction "13_13") (pintype "passive"))
    )
    (net (code "39") (name "Net-(R128-Pad1)") (class "Default")
      (node (ref "R128") (pin "1") (pinfunction "1_1") (pintype "passive"))
      (node (ref "RJ2") (pin "11") (pinfunction "11_11") (pintype "passive"))
    )
    (net (code "40") (name "Net-(U25-CFG_EXT)") (class "Default")
      (node (ref "R138") (pin "1") (pinfunction "1_1") (pintype "passive"))
      (node (ref "U25") (pin "32") (pinfunction "CFG_EXT_32") (pintype "passive"))
    )
    (net (code "41") (name "Net-(U25-NTB{slash}PMEB)") (class "Default")
      (node (ref "R134") (pin "1") (pinfunction "1_1") (pintype "passive"))
      (node (ref "TP2") (pin "1") (pinfunction "1_1") (pintype "passive"))
      (node (ref "U25") (pin "31") (pinfunction "NTB/PMEB_31") (pintype "passive"))
    )
    (net (code "42") (name "Net-(U25-REG_OUT)") (class "Default")
      (node (ref "L18") (pin "1") (pinfunction "1_1") (pintype "passive"))
      (node (ref "U25") (pin "30") (pinfunction "REG_OUT_30") (pintype "passive"))
    )
    (net (code "43") (name "Net-(U25-RSET)") (class "Default")
      (node (ref "R122") (pin "1") (pinfunction "1_1") (pintype "passive"))
      (node (ref "U25") (pin "39") (pinfunction "RSET_39") (pintype "passive"))
    )
    (net (code "44") (name "Net-(U25-XTAL_IN)") (class "Default")
      (node (ref "C271") (pin "1") (pinfunction "1_1") (pintype "passive"))
      (node (ref "U25") (pin "36") (pinfunction "XTAL_IN_36") (pintype "passive"))
      (node (ref "Y2") (pin "3") (pinfunction "3_3") (pintype "passive"))
    )
    (net (code "45") (name "Net-(U25-XTAL_OUT{slash}EXT_CLK)") (class "Default")
      (node (ref "C272") (pin "1") (pinfunction "1_1") (pintype "passive"))
      (node (ref "U25") (pin "37") (pinfunction "XTAL_OUT/EXT_CLK_37") (pintype "passive"))
      (node (ref "Y2") (pin "1") (pinfunction "1_1") (pintype "passive"))
    )
    (net (code "46") (name "VCC_1V8") (class "Default")
      (node (ref "L20") (pin "2") (pinfunction "2_2") (pintype "passive"))
    )
    (net (code "47") (name "VDD_3V3") (class "Default")
      (node (ref "L19") (pin "2") (pinfunction "2_2") (pintype "passive"))
      (node (ref "L21") (pin "2") (pinfunction "2_2") (pintype "passive"))
    )
  )
)
